# v4_1.net
KiCad netlist of a schematic drawn in EAGLE
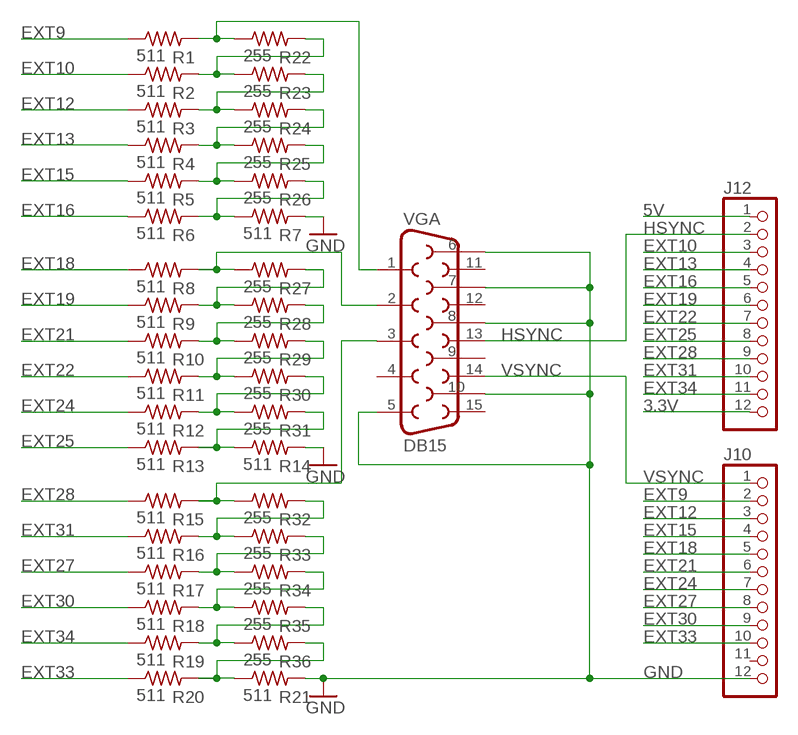
[diagram p0: schematic, sheet 1]

(export (version "E")
  (design (tool "Eeschema 10.0.6"))
  (components
    (comp (ref "J10")
      (value "PINHD-1X12")
      (footprint "eagle-import:1X12")
      (libsource (lib "eagle-import") (part "PINHD-1X12"))
    )
    (comp (ref "J12")
      (value "PINHD-1X12")
      (footprint "eagle-import:1X12")
      (libsource (lib "eagle-import") (part "PINHD-1X12"))
    )
    (comp (ref "R1")
      (value "511")
      (footprint "eagle-import:R0805")
      (libsource (lib "eagle-import") (part "R-US_R0805"))
    )
    (comp (ref "R2")
      (value "511")
      (footprint "eagle-import:R0805")
      (libsource (lib "eagle-import") (part "R-US_R0805"))
    )
    (comp (ref "R3")
      (value "511")
      (footprint "eagle-import:R0805")
      (libsource (lib "eagle-import") (part "R-US_R0805"))
    )
    (comp (ref "R4")
      (value "511")
      (footprint "eagle-import:R0805")
      (libsource (lib "eagle-import") (part "R-US_R0805"))
    )
    (comp (ref "R5")
      (value "511")
      (footprint "eagle-import:R0805")
      (libsource (lib "eagle-import") (part "R-US_R0805"))
    )
    (comp (ref "R6")
      (value "511")
      (footprint "eagle-import:R0805")
      (libsource (lib "eagle-import") (part "R-US_R0805"))
    )
    (comp (ref "R7")
      (value "511")
      (footprint "eagle-import:R0805")
      (libsource (lib "eagle-import") (part "R-US_R0805"))
    )
    (comp (ref "R8")
      (value "511")
      (footprint "eagle-import:R0805")
      (libsource (lib "eagle-import") (part "R-US_R0805"))
    )
    (comp (ref "R9")
      (value "511")
      (footprint "eagle-import:R0805")
      (libsource (lib "eagle-import") (part "R-US_R0805"))
    )
    (comp (ref "R10")
      (value "511")
      (footprint "eagle-import:R0805")
      (libsource (lib "eagle-import") (part "R-US_R0805"))
    )
    (comp (ref "R11")
      (value "511")
      (footprint "eagle-import:R0805")
      (libsource (lib "eagle-import") (part "R-US_R0805"))
    )
    (comp (ref "R12")
      (value "511")
      (footprint "eagle-import:R0805")
      (libsource (lib "eagle-import") (part "R-US_R0805"))
    )
    (comp (ref "R13")
      (value "511")
      (footprint "eagle-import:R0805")
      (libsource (lib "eagle-import") (part "R-US_R0805"))
    )
    (comp (ref "R14")
      (value "511")
      (footprint "eagle-import:R0805")
      (libsource (lib "eagle-import") (part "R-US_R0805"))
    )
    (comp (ref "R15")
      (value "511")
      (footprint "eagle-import:R0805")
      (libsource (lib "eagle-import") (part "R-US_R0805"))
    )
    (comp (ref "R16")
      (value "511")
      (footprint "eagle-import:R0805")
      (libsource (lib "eagle-import") (part "R-US_R0805"))
    )
    (comp (ref "R17")
      (value "511")
      (footprint "eagle-import:R0805")
      (libsource (lib "eagle-import") (part "R-US_R0805"))
    )
    (comp (ref "R18")
      (value "511")
      (footprint "eagle-import:R0805")
      (libsource (lib "eagle-import") (part "R-US_R0805"))
    )
    (comp (ref "R19")
      (value "511")
      (footprint "eagle-import:R0805")
      (libsource (lib "eagle-import") (part "R-US_R0805"))
    )
    (comp (ref "R20")
      (value "511")
      (footprint "eagle-import:R0805")
      (libsource (lib "eagle-import") (part "R-US_R0805"))
    )
    (comp (ref "R21")
      (value "511")
      (footprint "eagle-import:R0805")
      (libsource (lib "eagle-import") (part "R-US_R0805"))
    )
    (comp (ref "R22")
      (value "255")
      (footprint "eagle-import:R0805")
      (libsource (lib "eagle-import") (part "R-US_R0805"))
    )
    (comp (ref "R23")
      (value "255")
      (footprint "eagle-import:R0805")
      (libsource (lib "eagle-import") (part "R-US_R0805"))
    )
    (comp (ref "R24")
      (value "255")
      (footprint "eagle-import:R0805")
      (libsource (lib "eagle-import") (part "R-US_R0805"))
    )
    (comp (ref "R25")
      (value "255")
      (footprint "eagle-import:R0805")
      (libsource (lib "eagle-import") (part "R-US_R0805"))
    )
    (comp (ref "R26")
      (value "255")
      (footprint "eagle-import:R0805")
      (libsource (lib "eagle-import") (part "R-US_R0805"))
    )
    (comp (ref "R27")
      (value "255")
      (footprint "eagle-import:R0805")
      (libsource (lib "eagle-import") (part "R-US_R0805"))
    )
    (comp (ref "R28")
      (value "255")
      (footprint "eagle-import:R0805")
      (libsource (lib "eagle-import") (part "R-US_R0805"))
    )
    (comp (ref "R29")
      (value "255")
      (footprint "eagle-import:R0805")
      (libsource (lib "eagle-import") (part "R-US_R0805"))
    )
    (comp (ref "R30")
      (value "255")
      (footprint "eagle-import:R0805")
      (libsource (lib "eagle-import") (part "R-US_R0805"))
    )
    (comp (ref "R31")
      (value "255")
      (footprint "eagle-import:R0805")
      (libsource (lib "eagle-import") (part "R-US_R0805"))
    )
    (comp (ref "R32")
      (value "255")
      (footprint "eagle-import:R0805")
      (libsource (lib "eagle-import") (part "R-US_R0805"))
    )
    (comp (ref "R33")
      (value "255")
      (footprint "eagle-import:R0805")
      (libsource (lib "eagle-import") (part "R-US_R0805"))
    )
    (comp (ref "R34")
      (value "255")
      (footprint "eagle-import:R0805")
      (libsource (lib "eagle-import") (part "R-US_R0805"))
    )
    (comp (ref "R35")
      (value "255")
      (footprint "eagle-import:R0805")
      (libsource (lib "eagle-import") (part "R-US_R0805"))
    )
    (comp (ref "R36")
      (value "255")
      (footprint "eagle-import:R0805")
      (libsource (lib "eagle-import") (part "R-US_R0805"))
    )
    (comp (ref "VGA")
      (value "DB15")
      (footprint "eagle-import:DB15")
      (libsource (lib "eagle-import") (part "DB15"))
    )
  )
  (nets
    (net (code "1") (name "/3.3V") (class "Default")
      (node (ref "J12") (pin "12") (pinfunction "12_12") (pintype "passive"))
    )
    (net (code "2") (name "/5V") (class "Default")
      (node (ref "J12") (pin "1") (pinfunction "1_1") (pintype "passive"))
    )
    (net (code "3") (name "/EXT9") (class "Default")
      (node (ref "J10") (pin "2") (pinfunction "2_2") (pintype "passive"))
      (node (ref "R1") (pin "1") (pinfunction "1_1") (pintype "passive"))
    )
    (net (code "4") (name "/EXT10") (class "Default")
      (node (ref "J12") (pin "3") (pinfunction "3_3") (pintype "passive"))
      (node (ref "R2") (pin "1") (pinfunction "1_1") (pintype "passive"))
    )
    (net (code "5") (name "/EXT12") (class "Default")
      (node (ref "J10") (pin "3") (pinfunction "3_3") (pintype "passive"))
      (node (ref "R3") (pin "1") (pinfunction "1_1") (pintype "passive"))
    )
    (net (code "6") (name "/EXT13") (class "Default")
      (node (ref "J12") (pin "4") (pinfunction "4_4") (pintype "passive"))
      (node (ref "R4") (pin "1") (pinfunction "1_1") (pintype "passive"))
    )
    (net (code "7") (name "/EXT15") (class "Default")
      (node (ref "J10") (pin "4") (pinfunction "4_4") (pintype "passive"))
      (node (ref "R5") (pin "1") (pinfunction "1_1") (pintype "passive"))
    )
    (net (code "8") (name "/EXT16") (class "Default")
      (node (ref "J12") (pin "5") (pinfunction "5_5") (pintype "passive"))
      (node (ref "R6") (pin "1") (pinfunction "1_1") (pintype "passive"))
    )
    (net (code "9") (name "/EXT18") (class "Default")
      (node (ref "J10") (pin "5") (pinfunction "5_5") (pintype "passive"))
      (node (ref "R8") (pin "1") (pinfunction "1_1") (pintype "passive"))
    )
    (net (code "10") (name "/EXT19") (class "Default")
      (node (ref "J12") (pin "6") (pinfunction "6_6") (pintype "passive"))
      (node (ref "R9") (pin "1") (pinfunction "1_1") (pintype "passive"))
    )
    (net (code "11") (name "/EXT21") (class "Default")
      (node (ref "J10") (pin "6") (pinfunction "6_6") (pintype "passive"))
      (node (ref "R10") (pin "1") (pinfunction "1_1") (pintype "passive"))
    )
    (net (code "12") (name "/EXT22") (class "Default")
      (node (ref "J12") (pin "7") (pinfunction "7_7") (pintype "passive"))
      (node (ref "R11") (pin "1") (pinfunction "1_1") (pintype "passive"))
    )
    (net (code "13") (name "/EXT24") (class "Default")
      (node (ref "J10") (pin "7") (pinfunction "7_7") (pintype "passive"))
      (node (ref "R12") (pin "1") (pinfunction "1_1") (pintype "passive"))
    )
    (net (code "14") (name "/EXT25") (class "Default")
      (node (ref "J12") (pin "8") (pinfunction "8_8") (pintype "passive"))
      (node (ref "R13") (pin "1") (pinfunction "1_1") (pintype "passive"))
    )
    (net (code "15") (name "/EXT27") (class "Default")
      (node (ref "J10") (pin "8") (pinfunction "8_8") (pintype "passive"))
      (node (ref "R17") (pin "1") (pinfunction "1_1") (pintype "passive"))
    )
    (net (code "16") (name "/EXT28") (class "Default")
      (node (ref "J12") (pin "9") (pinfunction "9_9") (pintype "passive"))
      (node (ref "R15") (pin "1") (pinfunction "1_1") (pintype "passive"))
    )
    (net (code "17") (name "/EXT30") (class "Default")
      (node (ref "J10") (pin "9") (pinfunction "9_9") (pintype "passive"))
      (node (ref "R18") (pin "1") (pinfunction "1_1") (pintype "passive"))
    )
    (net (code "18") (name "/EXT31") (class "Default")
      (node (ref "J12") (pin "10") (pinfunction "10_10") (pintype "passive"))
      (node (ref "R16") (pin "1") (pinfunction "1_1") (pintype "passive"))
    )
    (net (code "19") (name "/EXT33") (class "Default")
      (node (ref "J10") (pin "10") (pinfunction "10_10") (pintype "passive"))
      (node (ref "R20") (pin "1") (pinfunction "1_1") (pintype "passive"))
    )
    (net (code "20") (name "/EXT34") (class "Default")
      (node (ref "J12") (pin "11") (pinfunction "11_11") (pintype "passive"))
      (node (ref "R19") (pin "1") (pinfunction "1_1") (pintype "passive"))
    )
    (net (code "21") (name "/HSYNC") (class "Default")
      (node (ref "J12") (pin "2") (pinfunction "2_2") (pintype "passive"))
      (node (ref "VGA") (pin "13") (pinfunction "13_13") (pintype "passive"))
    )
    (net (code "22") (name "/VSYNC") (class "Default")
      (node (ref "J10") (pin "1") (pinfunction "1_1") (pintype "passive"))
      (node (ref "VGA") (pin "14") (pinfunction "14_14") (pintype "passive"))
    )
    (net (code "23") (name "GND") (class "Default")
      (node (ref "J10") (pin "12") (pinfunction "12_12") (pintype "passive"))
      (node (ref "R14") (pin "2") (pinfunction "2_2") (pintype "passive"))
      (node (ref "R21") (pin "2") (pinfunction "2_2") (pintype "passive"))
      (node (ref "R7") (pin "2") (pinfunction "2_2") (pintype "passive"))
      (node (ref "VGA") (pin "10") (pinfunction "10_10") (pintype "passive"))
      (node (ref "VGA") (pin "5") (pinfunction "5_5") (pintype "passive"))
      (node (ref "VGA") (pin "6") (pinfunction "6_6") (pintype "passive"))
      (node (ref "VGA") (pin "7") (pinfunction "7_7") (pintype "passive"))
      (node (ref "VGA") (pin "8") (pinfunction "8_8") (pintype "passive"))
    )
    (net (code "24") (name "Net-(R1-Pad2)") (class "Default")
      (node (ref "R1") (pin "2") (pinfunction "2_2") (pintype "passive"))
      (node (ref "R22") (pin "1") (pinfunction "1_1") (pintype "passive"))
      (node (ref "VGA") (pin "1") (pinfunction "1_1") (pintype "passive"))
    )
    (net (code "25") (name "Net-(R2-Pad2)") (class "Default")
      (node (ref "R2") (pin "2") (pinfunction "2_2") (pintype "passive"))
      (node (ref "R22") (pin "2") (pinfunction "2_2") (pintype "passive"))
      (node (ref "R23") (pin "1") (pinfunction "1_1") (pintype "passive"))
    )
    (net (code "26") (name "Net-(R10-Pad2)") (class "Default")
      (node (ref "R10") (pin "2") (pinfunction "2_2") (pintype "passive"))
      (node (ref "R28") (pin "2") (pinfunction "2_2") (pintype "passive"))
      (node (ref "R29") (pin "1") (pinfunction "1_1") (pintype "passive"))
    )
    (net (code "27") (name "Net-(R11-Pad2)") (class "Default")
      (node (ref "R11") (pin "2") (pinfunction "2_2") (pintype "passive"))
      (node (ref "R29") (pin "2") (pinfunction "2_2") (pintype "passive"))
      (node (ref "R30") (pin "1") (pinfunction "1_1") (pintype "passive"))
    )
    (net (code "28") (name "Net-(R12-Pad2)") (class "Default")
      (node (ref "R12") (pin "2") (pinfunction "2_2") (pintype "passive"))
      (node (ref "R30") (pin "2") (pinfunction "2_2") (pintype "passive"))
      (node (ref "R31") (pin "1") (pinfunction "1_1") (pintype "passive"))
    )
    (net (code "29") (name "Net-(R13-Pad2)") (class "Default")
      (node (ref "R13") (pin "2") (pinfunction "2_2") (pintype "passive"))
      (node (ref "R14") (pin "1") (pinfunction "1_1") (pintype "passive"))
      (node (ref "R31") (pin "2") (pinfunction "2_2") (pintype "passive"))
    )
    (net (code "30") (name "Net-(R15-Pad2)") (class "Default")
      (node (ref "R15") (pin "2") (pinfunction "2_2") (pintype "passive"))
      (node (ref "R32") (pin "1") (pinfunction "1_1") (pintype "passive"))
      (node (ref "VGA") (pin "3") (pinfunction "3_3") (pintype "passive"))
    )
    (net (code "31") (name "Net-(R16-Pad2)") (class "Default")
      (node (ref "R16") (pin "2") (pinfunction "2_2") (pintype "passive"))
      (node (ref "R32") (pin "2") (pinfunction "2_2") (pintype "passive"))
      (node (ref "R33") (pin "1") (pinfunction "1_1") (pintype "passive"))
    )
    (net (code "32") (name "Net-(R17-Pad2)") (class "Default")
      (node (ref "R17") (pin "2") (pinfunction "2_2") (pintype "passive"))
      (node (ref "R33") (pin "2") (pinfunction "2_2") (pintype "passive"))
      (node (ref "R34") (pin "1") (pinfunction "1_1") (pintype "passive"))
    )
    (net (code "33") (name "Net-(R18-Pad2)") (class "Default")
      (node (ref "R18") (pin "2") (pinfunction "2_2") (pintype "passive"))
      (node (ref "R34") (pin "2") (pinfunction "2_2") (pintype "passive"))
      (node (ref "R35") (pin "1") (pinfunction "1_1") (pintype "passive"))
    )
    (net (code "34") (name "Net-(R19-Pad2)") (class "Default")
      (node (ref "R19") (pin "2") (pinfunction "2_2") (pintype "passive"))
      (node (ref "R35") (pin "2") (pinfunction "2_2") (pintype "passive"))
      (node (ref "R36") (pin "1") (pinfunction "1_1") (pintype "passive"))
    )
    (net (code "35") (name "Net-(R20-Pad2)") (class "Default")
      (node (ref "R20") (pin "2") (pinfunction "2_2") (pintype "passive"))
      (node (ref "R21") (pin "1") (pinfunction "1_1") (pintype "passive"))
      (node (ref "R36") (pin "2") (pinfunction "2_2") (pintype "passive"))
    )
    (net (code "36") (name "Net-(R23-Pad2)") (class "Default")
      (node (ref "R23") (pin "2") (pinfunction "2_2") (pintype "passive"))
      (node (ref "R24") (pin "1") (pinfunction "1_1") (pintype "passive"))
      (node (ref "R3") (pin "2") (pinfunction "2_2") (pintype "passive"))
    )
    (net (code "37") (name "Net-(R24-Pad2)") (class "Default")
      (node (ref "R24") (pin "2") (pinfunction "2_2") (pintype "passive"))
      (node (ref "R25") (pin "1") (pinfunction "1_1") (pintype "passive"))
      (node (ref "R4") (pin "2") (pinfunction "2_2") (pintype "passive"))
    )
    (net (code "38") (name "Net-(R25-Pad2)") (class "Default")
      (node (ref "R25") (pin "2") (pinfunction "2_2") (pintype "passive"))
      (node (ref "R26") (pin "1") (pinfunction "1_1") (pintype "passive"))
      (node (ref "R5") (pin "2") (pinfunction "2_2") (pintype "passive"))
    )
    (net (code "39") (name "Net-(R26-Pad2)") (class "Default")
      (node (ref "R26") (pin "2") (pinfunction "2_2") (pintype "passive"))
      (node (ref "R6") (pin "2") (pinfunction "2_2") (pintype "passive"))
      (node (ref "R7") (pin "1") (pinfunction "1_1") (pintype "passive"))
    )
    (net (code "40") (name "Net-(R27-Pad1)") (class "Default")
      (node (ref "R27") (pin "1") (pinfunction "1_1") (pintype "passive"))
      (node (ref "R8") (pin "2") (pinfunction "2_2") (pintype "passive"))
      (node (ref "VGA") (pin "2") (pinfunction "2_2") (pintype "passive"))
    )
    (net (code "41") (name "Net-(R27-Pad2)") (class "Default")
      (node (ref "R27") (pin "2") (pinfunction "2_2") (pintype "passive"))
      (node (ref "R28") (pin "1") (pinfunction "1_1") (pintype "passive"))
      (node (ref "R9") (pin "2") (pinfunction "2_2") (pintype "passive"))
    )
    (net (code "42") (name "unconnected-(J10-Pad11)") (class "Default")
      (node (ref "J10") (pin "11") (pinfunction "11_11") (pintype "passive"))
    )
    (net (code "43") (name "unconnected-(VGA-Pad4)") (class "Default")
      (node (ref "VGA") (pin "4") (pinfunction "4_4") (pintype "passive"))
    )
    (net (code "44") (name "unconnected-(VGA-Pad9)") (class "Default")
      (node (ref "VGA") (pin "9") (pinfunction "9_9") (pintype "passive"))
    )
    (net (code "45") (name "unconnected-(VGA-Pad11)") (class "Default")
      (node (ref "VGA") (pin "11") (pinfunction "11_11") (pintype "passive"))
    )
    (net (code "46") (name "unconnected-(VGA-Pad12)") (class "Default")
      (node (ref "VGA") (pin "12") (pinfunction "12_12") (pintype "passive"))
    )
    (net (code "47") (name "unconnected-(VGA-Pad15)") (class "Default")
      (node (ref "VGA") (pin "15") (pinfunction "15_15") (pintype "passive"))
    )
  )
)
